# design.net
KiCad netlist of a schematic drawn in Altium Designer
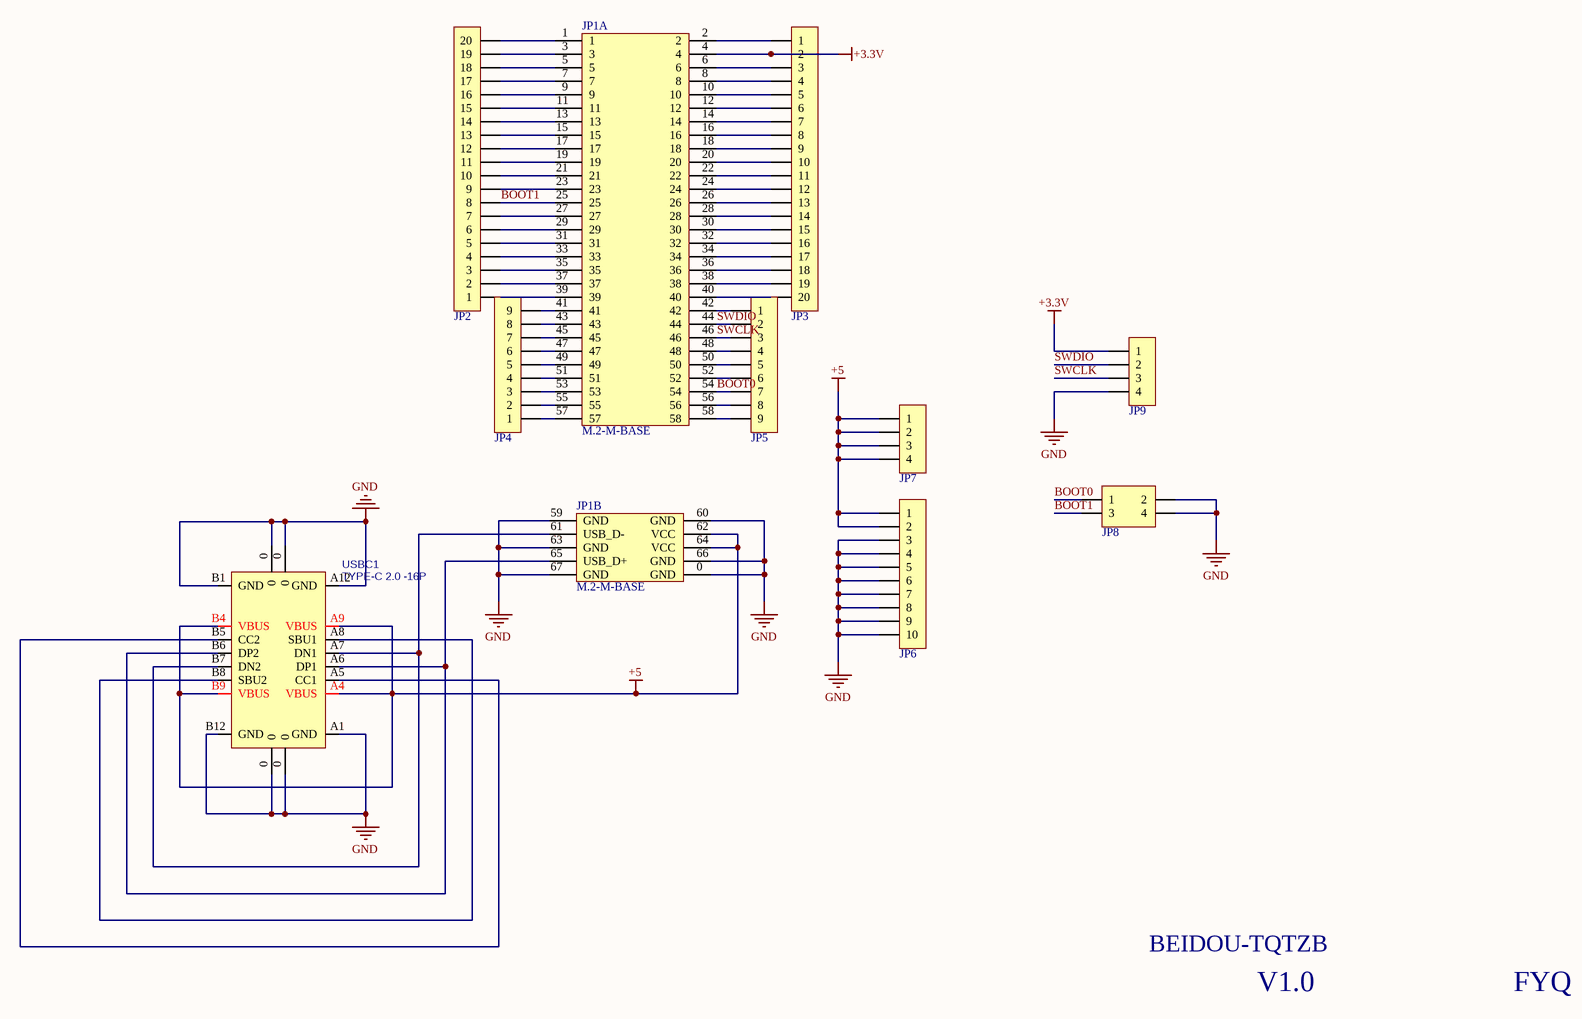
[diagram p0: 拓展板.SchDoc]

(export (version "E")
  (design (tool "Eeschema 10.0.6"))
  (components
    (comp (ref "JP1")
      (value "M.2-M-BASE")
      (footprint "M.2-MKEY-LI-底座")
      (description "M.2-M底座")
      (libsource (lib "M.2接口") (part "M.2-M底座"))
    )
    (comp (ref "JP2")
      (value "HDR-1X20")
      (footprint "HDR2.54-LI-20P")
      (description "20P接插件")
      (libsource (lib "5.4 - 接插件-脚距2.54 (100mil) ") (part "Header 20"))
    )
    (comp (ref "JP3")
      (value "HDR-1X20")
      (footprint "HDR2.54-LI-20P")
      (description "20P接插件")
      (libsource (lib "") (part "Header 20_1"))
    )
    (comp (ref "JP4")
      (value "HDR-1X9")
      (footprint "HDR2.54-LI-9P")
      (description "9P接插件")
      (libsource (lib "5.4 - 接插件-脚距2.54 (100mil) ") (part "Header 9"))
    )
    (comp (ref "JP5")
      (value "HDR-1X9")
      (footprint "HDR2.54-LI-9P")
      (description "9P接插件")
      (libsource (lib "") (part "Header 9_1"))
    )
    (comp (ref "JP6")
      (value "HDR-1X10")
      (footprint "HDR2.54-LI-10P")
      (description "10P接插件")
      (libsource (lib "5.4 - 接插件-脚距2.54 (100mil) ") (part "Header 10"))
    )
    (comp (ref "JP7")
      (value "HDR-1X4")
      (footprint "HDR2.54-LI-4P")
      (description "4P接插件")
      (libsource (lib "5.4 - 接插件-脚距2.54 (100mil) ") (part "Header 4"))
    )
    (comp (ref "JP8")
      (value "Header2X2")
      (footprint "HDR2.54-LI-2x2P")
      (description "2*2P接插件")
      (libsource (lib "5.4 - 接插件-脚距2.54 (100mil) ") (part "Header 2X2"))
    )
    (comp (ref "JP9")
      (value "HDR-1X4")
      (footprint "HDR2.54-LI-4P")
      (description "4P接插件")
      (libsource (lib "5.4 - 接插件-脚距2.54 (100mil) ") (part "Header 4"))
    )
    (comp (ref "USBC1")
      (value "TYPE-C 2.0 -16P")
      (footprint "USB-C-SMD_16P")
      (description "USB2.0 Type-C 16Pin  母座")
      (libsource (lib "0.8 - 以太网-音频-Type-C USB插座") (part "USB2.0_Type-C_16Pin"))
    )
  )
  (nets
    (net (code "1") (name "+3.3V") (class "Default")
      (node (ref "JP1") (pin "4") (pinfunction "4_4") (pintype "passive"))
      (node (ref "JP3") (pin "2") (pinfunction "2_2") (pintype "passive"))
      (node (ref "JP9") (pin "1") (pinfunction "1_1") (pintype "passive"))
    )
    (net (code "2") (name "+5") (class "Default")
      (node (ref "JP1") (pin "62") (pinfunction "VCC_62") (pintype "passive"))
      (node (ref "JP1") (pin "64") (pinfunction "VCC_64") (pintype "passive"))
      (node (ref "JP6") (pin "1") (pinfunction "1_1") (pintype "passive"))
      (node (ref "JP6") (pin "2") (pinfunction "2_2") (pintype "passive"))
      (node (ref "JP7") (pin "1") (pinfunction "1_1") (pintype "passive"))
      (node (ref "JP7") (pin "2") (pinfunction "2_2") (pintype "passive"))
      (node (ref "JP7") (pin "3") (pinfunction "3_3") (pintype "passive"))
      (node (ref "JP7") (pin "4") (pinfunction "4_4") (pintype "passive"))
      (node (ref "USBC1") (pin "A4") (pinfunction "VBUS_A4") (pintype "passive"))
      (node (ref "USBC1") (pin "A9") (pinfunction "VBUS_A9") (pintype "passive"))
      (node (ref "USBC1") (pin "B4") (pinfunction "VBUS_B4") (pintype "passive"))
      (node (ref "USBC1") (pin "B9") (pinfunction "VBUS_B9") (pintype "passive"))
    )
    (net (code "3") (name "/BOOT0") (class "Default")
      (node (ref "JP1") (pin "54") (pinfunction "54_54") (pintype "passive"))
      (node (ref "JP5") (pin "7") (pinfunction "7_7") (pintype "passive"))
      (node (ref "JP8") (pin "1") (pinfunction "1_1") (pintype "passive"))
    )
    (net (code "4") (name "/BOOT1") (class "Default")
      (node (ref "JP1") (pin "25") (pinfunction "25_25") (pintype "passive"))
      (node (ref "JP2") (pin "8") (pinfunction "8_8") (pintype "passive"))
      (node (ref "JP8") (pin "3") (pinfunction "3_3") (pintype "passive"))
    )
    (net (code "5") (name "/SWCLK") (class "Default")
      (node (ref "JP1") (pin "46") (pinfunction "46_46") (pintype "passive"))
      (node (ref "JP5") (pin "3") (pinfunction "3_3") (pintype "passive"))
      (node (ref "JP9") (pin "3") (pinfunction "3_3") (pintype "passive"))
    )
    (net (code "6") (name "/SWDIO") (class "Default")
      (node (ref "JP1") (pin "44") (pinfunction "44_44") (pintype "passive"))
      (node (ref "JP5") (pin "2") (pinfunction "2_2") (pintype "passive"))
      (node (ref "JP9") (pin "2") (pinfunction "2_2") (pintype "passive"))
    )
    (net (code "7") (name "GND") (class "Default")
      (node (ref "JP1") (pin "0") (pinfunction "GND_0") (pintype "passive"))
      (node (ref "JP1") (pin "59") (pinfunction "GND_59") (pintype "passive"))
      (node (ref "JP1") (pin "60") (pinfunction "GND_60") (pintype "passive"))
      (node (ref "JP1") (pin "63") (pinfunction "GND_63") (pintype "passive"))
      (node (ref "JP1") (pin "66") (pinfunction "GND_66") (pintype "passive"))
      (node (ref "JP1") (pin "67") (pinfunction "GND_67") (pintype "passive"))
      (node (ref "JP6") (pin "10") (pinfunction "10_10") (pintype "passive"))
      (node (ref "JP6") (pin "3") (pinfunction "3_3") (pintype "passive"))
      (node (ref "JP6") (pin "4") (pinfunction "4_4") (pintype "passive"))
      (node (ref "JP6") (pin "5") (pinfunction "5_5") (pintype "passive"))
      (node (ref "JP6") (pin "6") (pinfunction "6_6") (pintype "passive"))
      (node (ref "JP6") (pin "7") (pinfunction "7_7") (pintype "passive"))
      (node (ref "JP6") (pin "8") (pinfunction "8_8") (pintype "passive"))
      (node (ref "JP6") (pin "9") (pinfunction "9_9") (pintype "passive"))
      (node (ref "JP8") (pin "2") (pinfunction "2_2") (pintype "passive"))
      (node (ref "JP8") (pin "4") (pinfunction "4_4") (pintype "passive"))
      (node (ref "JP9") (pin "4") (pinfunction "4_4") (pintype "passive"))
      (node (ref "USBC1") (pin "0") (pinfunction "0_0") (pintype "passive"))
      (node (ref "USBC1") (pin "A1") (pinfunction "GND_A1") (pintype "passive"))
      (node (ref "USBC1") (pin "A12") (pinfunction "GND_A12") (pintype "passive"))
      (node (ref "USBC1") (pin "B1") (pinfunction "GND_B1") (pintype "passive"))
      (node (ref "USBC1") (pin "B12") (pinfunction "GND_B12") (pintype "passive"))
    )
    (net (code "8") (name "Net-(JP1-Pad1)") (class "Default")
      (node (ref "JP1") (pin "1") (pinfunction "1_1") (pintype "passive"))
      (node (ref "JP2") (pin "20") (pinfunction "20_20") (pintype "passive"))
    )
    (net (code "9") (name "Net-(JP1-Pad2)") (class "Default")
      (node (ref "JP1") (pin "2") (pinfunction "2_2") (pintype "passive"))
      (node (ref "JP3") (pin "1") (pinfunction "1_1") (pintype "passive"))
    )
    (net (code "10") (name "Net-(JP1-Pad3)") (class "Default")
      (node (ref "JP1") (pin "3") (pinfunction "3_3") (pintype "passive"))
      (node (ref "JP2") (pin "19") (pinfunction "19_19") (pintype "passive"))
    )
    (net (code "11") (name "Net-(JP1-Pad5)") (class "Default")
      (node (ref "JP1") (pin "5") (pinfunction "5_5") (pintype "passive"))
      (node (ref "JP2") (pin "18") (pinfunction "18_18") (pintype "passive"))
    )
    (net (code "12") (name "Net-(JP1-Pad6)") (class "Default")
      (node (ref "JP1") (pin "6") (pinfunction "6_6") (pintype "passive"))
      (node (ref "JP3") (pin "3") (pinfunction "3_3") (pintype "passive"))
    )
    (net (code "13") (name "Net-(JP1-Pad7)") (class "Default")
      (node (ref "JP1") (pin "7") (pinfunction "7_7") (pintype "passive"))
      (node (ref "JP2") (pin "17") (pinfunction "17_17") (pintype "passive"))
    )
    (net (code "14") (name "Net-(JP1-Pad8)") (class "Default")
      (node (ref "JP1") (pin "8") (pinfunction "8_8") (pintype "passive"))
      (node (ref "JP3") (pin "4") (pinfunction "4_4") (pintype "passive"))
    )
    (net (code "15") (name "Net-(JP1-Pad9)") (class "Default")
      (node (ref "JP1") (pin "9") (pinfunction "9_9") (pintype "passive"))
      (node (ref "JP2") (pin "16") (pinfunction "16_16") (pintype "passive"))
    )
    (net (code "16") (name "Net-(JP1-Pad10)") (class "Default")
      (node (ref "JP1") (pin "10") (pinfunction "10_10") (pintype "passive"))
      (node (ref "JP3") (pin "5") (pinfunction "5_5") (pintype "passive"))
    )
    (net (code "17") (name "Net-(JP1-Pad11)") (class "Default")
      (node (ref "JP1") (pin "11") (pinfunction "11_11") (pintype "passive"))
      (node (ref "JP2") (pin "15") (pinfunction "15_15") (pintype "passive"))
    )
    (net (code "18") (name "Net-(JP1-Pad12)") (class "Default")
      (node (ref "JP1") (pin "12") (pinfunction "12_12") (pintype "passive"))
      (node (ref "JP3") (pin "6") (pinfunction "6_6") (pintype "passive"))
    )
    (net (code "19") (name "Net-(JP1-Pad13)") (class "Default")
      (node (ref "JP1") (pin "13") (pinfunction "13_13") (pintype "passive"))
      (node (ref "JP2") (pin "14") (pinfunction "14_14") (pintype "passive"))
    )
    (net (code "20") (name "Net-(JP1-Pad14)") (class "Default")
      (node (ref "JP1") (pin "14") (pinfunction "14_14") (pintype "passive"))
      (node (ref "JP3") (pin "7") (pinfunction "7_7") (pintype "passive"))
    )
    (net (code "21") (name "Net-(JP1-Pad15)") (class "Default")
      (node (ref "JP1") (pin "15") (pinfunction "15_15") (pintype "passive"))
      (node (ref "JP2") (pin "13") (pinfunction "13_13") (pintype "passive"))
    )
    (net (code "22") (name "Net-(JP1-Pad16)") (class "Default")
      (node (ref "JP1") (pin "16") (pinfunction "16_16") (pintype "passive"))
      (node (ref "JP3") (pin "8") (pinfunction "8_8") (pintype "passive"))
    )
    (net (code "23") (name "Net-(JP1-Pad17)") (class "Default")
      (node (ref "JP1") (pin "17") (pinfunction "17_17") (pintype "passive"))
      (node (ref "JP2") (pin "12") (pinfunction "12_12") (pintype "passive"))
    )
    (net (code "24") (name "Net-(JP1-Pad18)") (class "Default")
      (node (ref "JP1") (pin "18") (pinfunction "18_18") (pintype "passive"))
      (node (ref "JP3") (pin "9") (pinfunction "9_9") (pintype "passive"))
    )
    (net (code "25") (name "Net-(JP1-Pad19)") (class "Default")
      (node (ref "JP1") (pin "19") (pinfunction "19_19") (pintype "passive"))
      (node (ref "JP2") (pin "11") (pinfunction "11_11") (pintype "passive"))
    )
    (net (code "26") (name "Net-(JP1-Pad20)") (class "Default")
      (node (ref "JP1") (pin "20") (pinfunction "20_20") (pintype "passive"))
      (node (ref "JP3") (pin "10") (pinfunction "10_10") (pintype "passive"))
    )
    (net (code "27") (name "Net-(JP1-Pad21)") (class "Default")
      (node (ref "JP1") (pin "21") (pinfunction "21_21") (pintype "passive"))
      (node (ref "JP2") (pin "10") (pinfunction "10_10") (pintype "passive"))
    )
    (net (code "28") (name "Net-(JP1-Pad22)") (class "Default")
      (node (ref "JP1") (pin "22") (pinfunction "22_22") (pintype "passive"))
      (node (ref "JP3") (pin "11") (pinfunction "11_11") (pintype "passive"))
    )
    (net (code "29") (name "Net-(JP1-Pad23)") (class "Default")
      (node (ref "JP1") (pin "23") (pinfunction "23_23") (pintype "passive"))
      (node (ref "JP2") (pin "9") (pinfunction "9_9") (pintype "passive"))
    )
    (net (code "30") (name "Net-(JP1-Pad24)") (class "Default")
      (node (ref "JP1") (pin "24") (pinfunction "24_24") (pintype "passive"))
      (node (ref "JP3") (pin "12") (pinfunction "12_12") (pintype "passive"))
    )
    (net (code "31") (name "Net-(JP1-Pad26)") (class "Default")
      (node (ref "JP1") (pin "26") (pinfunction "26_26") (pintype "passive"))
      (node (ref "JP3") (pin "13") (pinfunction "13_13") (pintype "passive"))
    )
    (net (code "32") (name "Net-(JP1-Pad27)") (class "Default")
      (node (ref "JP1") (pin "27") (pinfunction "27_27") (pintype "passive"))
      (node (ref "JP2") (pin "7") (pinfunction "7_7") (pintype "passive"))
    )
    (net (code "33") (name "Net-(JP1-Pad28)") (class "Default")
      (node (ref "JP1") (pin "28") (pinfunction "28_28") (pintype "passive"))
      (node (ref "JP3") (pin "14") (pinfunction "14_14") (pintype "passive"))
    )
    (net (code "34") (name "Net-(JP1-Pad29)") (class "Default")
      (node (ref "JP1") (pin "29") (pinfunction "29_29") (pintype "passive"))
      (node (ref "JP2") (pin "6") (pinfunction "6_6") (pintype "passive"))
    )
    (net (code "35") (name "Net-(JP1-Pad30)") (class "Default")
      (node (ref "JP1") (pin "30") (pinfunction "30_30") (pintype "passive"))
      (node (ref "JP3") (pin "15") (pinfunction "15_15") (pintype "passive"))
    )
    (net (code "36") (name "Net-(JP1-Pad31)") (class "Default")
      (node (ref "JP1") (pin "31") (pinfunction "31_31") (pintype "passive"))
      (node (ref "JP2") (pin "5") (pinfunction "5_5") (pintype "passive"))
    )
    (net (code "37") (name "Net-(JP1-Pad32)") (class "Default")
      (node (ref "JP1") (pin "32") (pinfunction "32_32") (pintype "passive"))
      (node (ref "JP3") (pin "16") (pinfunction "16_16") (pintype "passive"))
    )
    (net (code "38") (name "Net-(JP1-Pad33)") (class "Default")
      (node (ref "JP1") (pin "33") (pinfunction "33_33") (pintype "passive"))
      (node (ref "JP2") (pin "4") (pinfunction "4_4") (pintype "passive"))
    )
    (net (code "39") (name "Net-(JP1-Pad34)") (class "Default")
      (node (ref "JP1") (pin "34") (pinfunction "34_34") (pintype "passive"))
      (node (ref "JP3") (pin "17") (pinfunction "17_17") (pintype "passive"))
    )
    (net (code "40") (name "Net-(JP1-Pad35)") (class "Default")
      (node (ref "JP1") (pin "35") (pinfunction "35_35") (pintype "passive"))
      (node (ref "JP2") (pin "3") (pinfunction "3_3") (pintype "passive"))
    )
    (net (code "41") (name "Net-(JP1-Pad36)") (class "Default")
      (node (ref "JP1") (pin "36") (pinfunction "36_36") (pintype "passive"))
      (node (ref "JP3") (pin "18") (pinfunction "18_18") (pintype "passive"))
    )
    (net (code "42") (name "Net-(JP1-Pad37)") (class "Default")
      (node (ref "JP1") (pin "37") (pinfunction "37_37") (pintype "passive"))
      (node (ref "JP2") (pin "2") (pinfunction "2_2") (pintype "passive"))
    )
    (net (code "43") (name "Net-(JP1-Pad38)") (class "Default")
      (node (ref "JP1") (pin "38") (pinfunction "38_38") (pintype "passive"))
      (node (ref "JP3") (pin "19") (pinfunction "19_19") (pintype "passive"))
    )
    (net (code "44") (name "Net-(JP1-Pad39)") (class "Default")
      (node (ref "JP1") (pin "39") (pinfunction "39_39") (pintype "passive"))
      (node (ref "JP2") (pin "1") (pinfunction "1_1") (pintype "passive"))
    )
    (net (code "45") (name "Net-(JP1-Pad40)") (class "Default")
      (node (ref "JP1") (pin "40") (pinfunction "40_40") (pintype "passive"))
      (node (ref "JP3") (pin "20") (pinfunction "20_20") (pintype "passive"))
    )
    (net (code "46") (name "Net-(JP1-Pad41)") (class "Default")
      (node (ref "JP1") (pin "41") (pinfunction "41_41") (pintype "passive"))
      (node (ref "JP4") (pin "9") (pinfunction "9_9") (pintype "passive"))
    )
    (net (code "47") (name "Net-(JP1-Pad42)") (class "Default")
      (node (ref "JP1") (pin "42") (pinfunction "42_42") (pintype "passive"))
      (node (ref "JP5") (pin "1") (pinfunction "1_1") (pintype "passive"))
    )
    (net (code "48") (name "Net-(JP1-Pad43)") (class "Default")
      (node (ref "JP1") (pin "43") (pinfunction "43_43") (pintype "passive"))
      (node (ref "JP4") (pin "8") (pinfunction "8_8") (pintype "passive"))
    )
    (net (code "49") (name "Net-(JP1-Pad45)") (class "Default")
      (node (ref "JP1") (pin "45") (pinfunction "45_45") (pintype "passive"))
      (node (ref "JP4") (pin "7") (pinfunction "7_7") (pintype "passive"))
    )
    (net (code "50") (name "Net-(JP1-Pad47)") (class "Default")
      (node (ref "JP1") (pin "47") (pinfunction "47_47") (pintype "passive"))
      (node (ref "JP4") (pin "6") (pinfunction "6_6") (pintype "passive"))
    )
    (net (code "51") (name "Net-(JP1-Pad48)") (class "Default")
      (node (ref "JP1") (pin "48") (pinfunction "48_48") (pintype "passive"))
      (node (ref "JP5") (pin "4") (pinfunction "4_4") (pintype "passive"))
    )
    (net (code "52") (name "Net-(JP1-Pad49)") (class "Default")
      (node (ref "JP1") (pin "49") (pinfunction "49_49") (pintype "passive"))
      (node (ref "JP4") (pin "5") (pinfunction "5_5") (pintype "passive"))
    )
    (net (code "53") (name "Net-(JP1-Pad50)") (class "Default")
      (node (ref "JP1") (pin "50") (pinfunction "50_50") (pintype "passive"))
      (node (ref "JP5") (pin "5") (pinfunction "5_5") (pintype "passive"))
    )
    (net (code "54") (name "Net-(JP1-Pad51)") (class "Default")
      (node (ref "JP1") (pin "51") (pinfunction "51_51") (pintype "passive"))
      (node (ref "JP4") (pin "4") (pinfunction "4_4") (pintype "passive"))
    )
    (net (code "55") (name "Net-(JP1-Pad52)") (class "Default")
      (node (ref "JP1") (pin "52") (pinfunction "52_52") (pintype "passive"))
      (node (ref "JP5") (pin "6") (pinfunction "6_6") (pintype "passive"))
    )
    (net (code "56") (name "Net-(JP1-Pad53)") (class "Default")
      (node (ref "JP1") (pin "53") (pinfunction "53_53") (pintype "passive"))
      (node (ref "JP4") (pin "3") (pinfunction "3_3") (pintype "passive"))
    )
    (net (code "57") (name "Net-(JP1-Pad55)") (class "Default")
      (node (ref "JP1") (pin "55") (pinfunction "55_55") (pintype "passive"))
      (node (ref "JP4") (pin "2") (pinfunction "2_2") (pintype "passive"))
    )
    (net (code "58") (name "Net-(JP1-Pad56)") (class "Default")
      (node (ref "JP1") (pin "56") (pinfunction "56_56") (pintype "passive"))
      (node (ref "JP5") (pin "8") (pinfunction "8_8") (pintype "passive"))
    )
    (net (code "59") (name "Net-(JP1-Pad57)") (class "Default")
      (node (ref "JP1") (pin "57") (pinfunction "57_57") (pintype "passive"))
      (node (ref "JP4") (pin "1") (pinfunction "1_1") (pintype "passive"))
    )
    (net (code "60") (name "Net-(JP1-Pad58)") (class "Default")
      (node (ref "JP1") (pin "58") (pinfunction "58_58") (pintype "passive"))
      (node (ref "JP5") (pin "9") (pinfunction "9_9") (pintype "passive"))
    )
    (net (code "61") (name "Net-(JP1B-USB_D+)") (class "Default")
      (node (ref "JP1") (pin "65") (pinfunction "USB_D+_65") (pintype "passive"))
      (node (ref "USBC1") (pin "A6") (pinfunction "DP1_A6") (pintype "passive"))
      (node (ref "USBC1") (pin "B6") (pinfunction "DP2_B6") (pintype "passive"))
    )
    (net (code "62") (name "Net-(JP1B-USB_D-)") (class "Default")
      (node (ref "JP1") (pin "61") (pinfunction "USB_D-_61") (pintype "passive"))
      (node (ref "USBC1") (pin "A7") (pinfunction "DN1_A7") (pintype "passive"))
      (node (ref "USBC1") (pin "B7") (pinfunction "DN2_B7") (pintype "passive"))
    )
    (net (code "63") (name "Net-(USBC1-CC1)") (class "Default")
      (node (ref "USBC1") (pin "A5") (pinfunction "CC1_A5") (pintype "passive"))
      (node (ref "USBC1") (pin "B5") (pinfunction "CC2_B5") (pintype "passive"))
    )
    (net (code "64") (name "Net-(USBC1-SBU1)") (class "Default")
      (node (ref "USBC1") (pin "A8") (pinfunction "SBU1_A8") (pintype "passive"))
      (node (ref "USBC1") (pin "B8") (pinfunction "SBU2_B8") (pintype "passive"))
    )
  )
)
